# led_ring.net
KiCad netlist of a schematic drawn in EAGLE
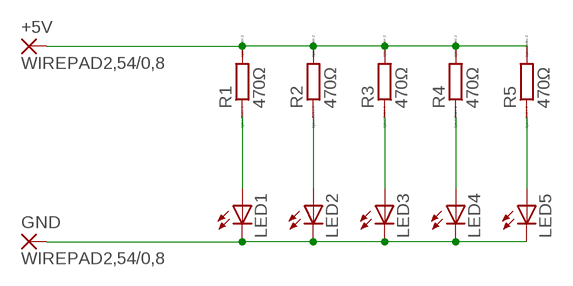
[diagram p0: schematic, sheet 1]

(export (version "E")
  (design (tool "Eeschema 10.0.6"))
  (components
    (comp (ref "+5V")
      (value "WIREPAD2,54/0,8")
      (footprint "eagle-import:2,54_0,8")
      (libsource (lib "eagle-import") (part "WIREPAD2,54/0,8"))
    )
    (comp (ref "GND")
      (value "WIREPAD2,54/0,8")
      (footprint "eagle-import:2,54_0,8")
      (libsource (lib "eagle-import") (part "WIREPAD2,54/0,8"))
    )
    (comp (ref "LED1")
      (value "LED5MM")
      (footprint "eagle-import:LED5MM")
      (libsource (lib "eagle-import") (part "LED5MM"))
    )
    (comp (ref "LED2")
      (value "LED5MM")
      (footprint "eagle-import:LED5MM")
      (libsource (lib "eagle-import") (part "LED5MM"))
    )
    (comp (ref "LED3")
      (value "LED5MM")
      (footprint "eagle-import:LED5MM")
      (libsource (lib "eagle-import") (part "LED5MM"))
    )
    (comp (ref "LED4")
      (value "LED5MM")
      (footprint "eagle-import:LED5MM")
      (libsource (lib "eagle-import") (part "LED5MM"))
    )
    (comp (ref "LED5")
      (value "LED5MM")
      (footprint "eagle-import:LED5MM")
      (libsource (lib "eagle-import") (part "LED5MM"))
    )
    (comp (ref "R1")
      (value "470Ω")
      (footprint "eagle-import:0204_7")
      (libsource (lib "eagle-import") (part "R0204/7"))
    )
    (comp (ref "R2")
      (value "470Ω")
      (footprint "eagle-import:0204_7")
      (libsource (lib "eagle-import") (part "R0204/7"))
    )
    (comp (ref "R3")
      (value "470Ω")
      (footprint "eagle-import:0204_7")
      (libsource (lib "eagle-import") (part "R0204/7"))
    )
    (comp (ref "R4")
      (value "470Ω")
      (footprint "eagle-import:0204_7")
      (libsource (lib "eagle-import") (part "R0204/7"))
    )
    (comp (ref "R5")
      (value "470Ω")
      (footprint "eagle-import:0204_7")
      (libsource (lib "eagle-import") (part "R0204/7"))
    )
  )
  (nets
    (net (code "1") (name "Net-(+5V-P)") (class "Default")
      (node (ref "+5V") (pin "1") (pinfunction "P_1") (pintype "passive"))
      (node (ref "R1") (pin "2") (pinfunction "2_2") (pintype "passive"))
      (node (ref "R2") (pin "2") (pinfunction "2_2") (pintype "passive"))
      (node (ref "R3") (pin "2") (pinfunction "2_2") (pintype "passive"))
      (node (ref "R4") (pin "2") (pinfunction "2_2") (pintype "passive"))
      (node (ref "R5") (pin "2") (pinfunction "2_2") (pintype "passive"))
    )
    (net (code "2") (name "Net-(GND-P)") (class "Default")
      (node (ref "GND") (pin "1") (pinfunction "P_1") (pintype "passive"))
      (node (ref "LED1") (pin "K") (pinfunction "C_K") (pintype "passive"))
      (node (ref "LED2") (pin "K") (pinfunction "C_K") (pintype "passive"))
      (node (ref "LED3") (pin "K") (pinfunction "C_K") (pintype "passive"))
      (node (ref "LED4") (pin "K") (pinfunction "C_K") (pintype "passive"))
      (node (ref "LED5") (pin "K") (pinfunction "C_K") (pintype "passive"))
    )
    (net (code "3") (name "Net-(LED1-PadA)") (class "Default")
      (node (ref "LED1") (pin "A") (pinfunction "A_A") (pintype "passive"))
      (node (ref "R1") (pin "1") (pinfunction "1_1") (pintype "passive"))
    )
    (net (code "4") (name "Net-(LED2-PadA)") (class "Default")
      (node (ref "LED2") (pin "A") (pinfunction "A_A") (pintype "passive"))
      (node (ref "R2") (pin "1") (pinfunction "1_1") (pintype "passive"))
    )
    (net (code "5") (name "Net-(LED3-PadA)") (class "Default")
      (node (ref "LED3") (pin "A") (pinfunction "A_A") (pintype "passive"))
      (node (ref "R3") (pin "1") (pinfunction "1_1") (pintype "passive"))
    )
    (net (code "6") (name "Net-(LED4-PadA)") (class "Default")
      (node (ref "LED4") (pin "A") (pinfunction "A_A") (pintype "passive"))
      (node (ref "R4") (pin "1") (pinfunction "1_1") (pintype "passive"))
    )
    (net (code "7") (name "Net-(LED5-PadA)") (class "Default")
      (node (ref "LED5") (pin "A") (pinfunction "A_A") (pintype "passive"))
      (node (ref "R5") (pin "1") (pinfunction "1_1") (pintype "passive"))
    )
  )
)
